# Power.net
KiCad netlist of a schematic drawn in Altium Designer
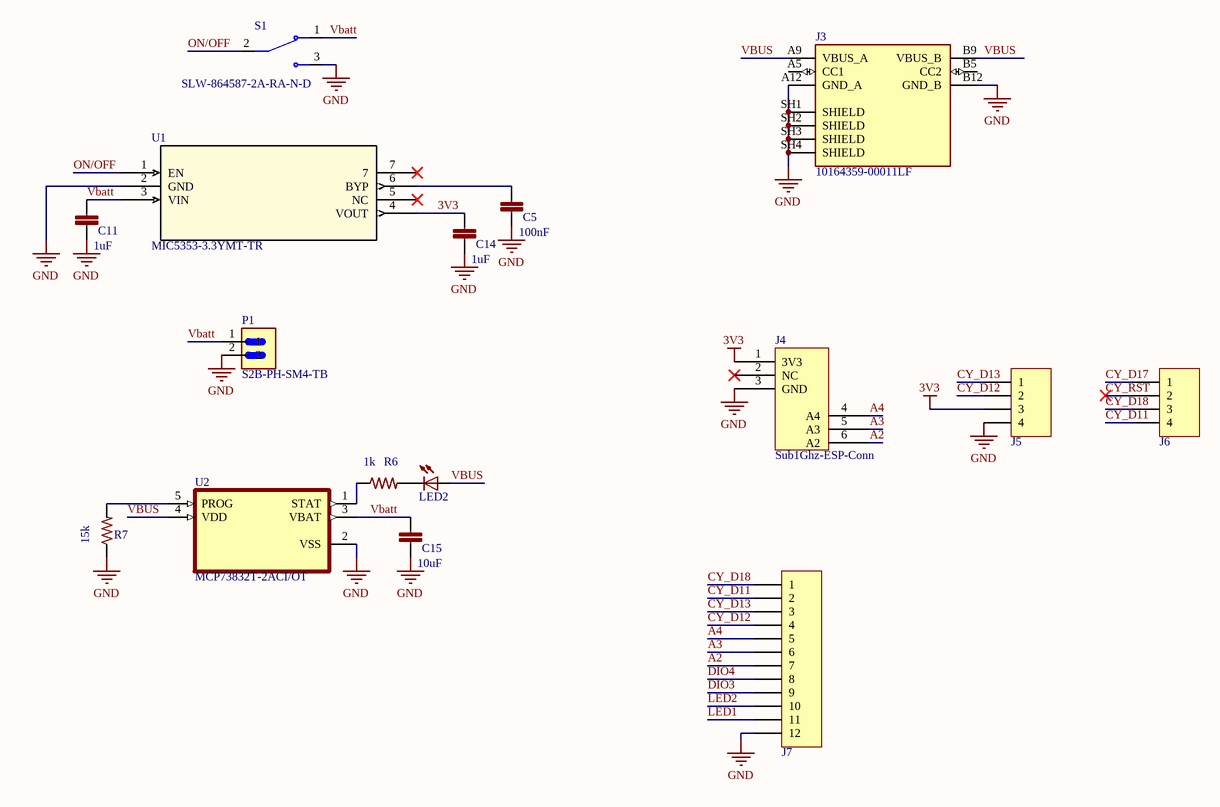
[diagram p0: Power.SchDoc]

(export (version "E")
  (design (tool "Eeschema 10.0.6"))
  (components
    (comp (ref "C5")
      (value "100nF")
      (footprint "C0402 - rounded")
      (description "Generic Capacitor SMD")
      (libsource (lib "rcl") (part "C-EU-SMD"))
    )
    (comp (ref "C11")
      (value "1uF")
      (footprint "C0402 - rounded")
      (description "Generic Capacitor SMD")
      (libsource (lib "rcl") (part "C-EU-SMD"))
    )
    (comp (ref "C14")
      (value "1uF")
      (footprint "C0402 - rounded")
      (description "Generic Capacitor SMD")
      (libsource (lib "rcl") (part "C-EU-SMD"))
    )
    (comp (ref "C15")
      (value "10uF")
      (footprint "C0603 - rounded")
      (description "Generic Capacitor SMD")
      (libsource (lib "rcl") (part "C-EU-SMD"))
    )
    (comp (ref "J3")
      (value "10164359-00011LF")
      (footprint "AMPHENOL_10164359-00011LF")
      (description "USB Type C Receptacle SMT Single Row 6Pin")
      (fields (field (name "MF") "Amphenol") (field (name "MP") "1016435900011LF"))
      (libsource (lib "Comm_Connectors") (part "10164359-00011LF"))
    )
    (comp (ref "J4")
      (value "Sub1Ghz-ESP-Conn")
      (footprint "Sub1GHz-ESP-Conn")
      (libsource (lib "Misc") (part "Sub1Ghz-ESP-Conn"))
    )
    (comp (ref "J5")
      (value "04p")
      (footprint "61300411121")
      (description "WR-PHD 2.54 mm THT Pin Header, 04p")
      (fields (field (name "PART NUMBER") "61300411121"))
      (libsource (lib "Header-254mm") (part "61300411121"))
    )
    (comp (ref "J6")
      (value "04p")
      (footprint "61300411121")
      (description "WR-PHD 2.54 mm THT Pin Header, 04p")
      (fields (field (name "PART NUMBER") "61300411121"))
      (libsource (lib "Header-254mm") (part "61300411121"))
    )
    (comp (ref "J7")
      (value "12p")
      (footprint "61301211821")
      (description "WR-PHD 2.54 mm Socket Header, 12p")
      (fields (field (name "PART NUMBER") "61301211821"))
      (libsource (lib "Header-254mm") (part "61301211821"))
    )
    (comp (ref "LED2")
      (value "LEDCHIPLED_1206")
      (footprint "CHIPLED_1206")
      (libsource (lib "led") (part "LEDCHIPLED_1206"))
    )
    (comp (ref "P1")
      (value "S2B-PH-SM4-TB")
      (footprint "JST_S2B-PH-SM4-TB")
      (description "Connector Header Surface Mount, Right Angle 2 position 0.079 (2.00mm)")
      (fields (field (name "MF") "JST Sales"))
      (libsource (lib "Misc") (part "S2B-PH-SM4-TB"))
    )
    (comp (ref "R6")
      (value "1k")
      (footprint "R0603 - rounded")
      (description "Generic Resistor SMD")
      (libsource (lib "rcl") (part "R-US-SMD"))
    )
    (comp (ref "R7")
      (value "15k")
      (footprint "R0603 - rounded")
      (description "Generic Resistor SMD")
      (libsource (lib "rcl") (part "R-US-SMD"))
    )
    (comp (ref "S1")
      (value "SLW-864587-2A-RA-N-D")
      (footprint "SW_SLW-864587-2A-RA-N-D")
      (description "8.6 x 4.5 x 8.7 mm, 2 mm Raised Slide Actuator, Right Angle, Through Hole, Slide Switch")
      (fields (field (name "MF") "Same Sky"))
      (libsource (lib "Misc") (part "SLW-864587-2A-RA-N-D"))
    )
    (comp (ref "U1")
      (value "MIC5353-3.3YMT-TR")
      (footprint "MLF-6_MT_MCH-M")
      (description "Description")
      (fields (field (name "COPYRIGHT") "Copyright (C) 2025 Ultra Librarian. All rights reserved."))
      (libsource (lib "Misc") (part "MIC5353-3.3YMT-TR"))
    )
    (comp (ref "U2")
      (value "MCP73832T-2ACI/OT")
      (footprint "SOT95P270X145-5N")
      (description "Linear Battery Charger Controller Li-Ion/Li-Pol 505mA 4.2V 5-Pin SOT-23 T/R")
      (fields (field (name "MF") "Microchip Technology"))
      (libsource (lib "Misc") (part "MCP73832T-2ACI/OT"))
    )
  )
  (nets
    (net (code "1") (name "/A2") (class "Default")
      (node (ref "J4") (pin "6") (pinfunction "A2_6") (pintype "passive"))
      (node (ref "J7") (pin "7") (pinfunction "7_7") (pintype "passive"))
    )
    (net (code "2") (name "/A3") (class "Default")
      (node (ref "J4") (pin "5") (pinfunction "A3_5") (pintype "passive"))
      (node (ref "J7") (pin "6") (pinfunction "6_6") (pintype "passive"))
    )
    (net (code "3") (name "/A4") (class "Default")
      (node (ref "J4") (pin "4") (pinfunction "A4_4") (pintype "passive"))
      (node (ref "J7") (pin "5") (pinfunction "5_5") (pintype "passive"))
    )
    (net (code "4") (name "/CY_D11") (class "Default")
      (node (ref "J6") (pin "4") (pinfunction "4_4") (pintype "passive"))
      (node (ref "J7") (pin "2") (pinfunction "2_2") (pintype "passive"))
    )
    (net (code "5") (name "/CY_D12") (class "Default")
      (node (ref "J5") (pin "2") (pinfunction "2_2") (pintype "passive"))
      (node (ref "J7") (pin "4") (pinfunction "4_4") (pintype "passive"))
    )
    (net (code "6") (name "/CY_D13") (class "Default")
      (node (ref "J5") (pin "1") (pinfunction "1_1") (pintype "passive"))
      (node (ref "J7") (pin "3") (pinfunction "3_3") (pintype "passive"))
    )
    (net (code "7") (name "/CY_D17") (class "Default")
      (node (ref "J6") (pin "1") (pinfunction "1_1") (pintype "passive"))
    )
    (net (code "8") (name "/CY_D18") (class "Default")
      (node (ref "J6") (pin "3") (pinfunction "3_3") (pintype "passive"))
      (node (ref "J7") (pin "1") (pinfunction "1_1") (pintype "passive"))
    )
    (net (code "9") (name "/CY_RST") (class "Default")
      (node (ref "J6") (pin "2") (pinfunction "2_2") (pintype "passive+no_connect"))
    )
    (net (code "10") (name "/DIO3") (class "Default")
      (node (ref "J7") (pin "9") (pinfunction "9_9") (pintype "passive"))
    )
    (net (code "11") (name "/DIO4") (class "Default")
      (node (ref "J7") (pin "8") (pinfunction "8_8") (pintype "passive"))
    )
    (net (code "12") (name "/LED1") (class "Default")
      (node (ref "J7") (pin "11") (pinfunction "11_11") (pintype "passive"))
    )
    (net (code "13") (name "/LED2") (class "Default")
      (node (ref "J7") (pin "10") (pinfunction "10_10") (pintype "passive"))
    )
    (net (code "14") (name "/ON{slash}OFF") (class "Default")
      (node (ref "S1") (pin "2") (pinfunction "2_2") (pintype "passive"))
      (node (ref "U1") (pin "1") (pinfunction "EN_1") (pintype "input"))
    )
    (net (code "15") (name "/VBUS") (class "Default")
      (node (ref "J3") (pin "A9") (pinfunction "VBUS_A_A9") (pintype "power_in"))
      (node (ref "J3") (pin "B9") (pinfunction "VBUS_B_B9") (pintype "power_in"))
      (node (ref "LED2") (pin "A") (pinfunction "A_A") (pintype "passive"))
      (node (ref "U2") (pin "4") (pinfunction "VDD_4") (pintype "input"))
    )
    (net (code "16") (name "/Vbatt") (class "Default")
      (node (ref "C11") (pin "1") (pinfunction "1_1") (pintype "passive"))
      (node (ref "C15") (pin "1") (pinfunction "1_1") (pintype "passive"))
      (node (ref "P1") (pin "1") (pinfunction "1_1") (pintype "passive"))
      (node (ref "S1") (pin "1") (pinfunction "1_1") (pintype "passive"))
      (node (ref "U1") (pin "3") (pinfunction "VIN_3") (pintype "input"))
      (node (ref "U2") (pin "3") (pinfunction "VBAT_3") (pintype "output"))
    )
    (net (code "17") (name "3V3") (class "Default")
      (node (ref "C14") (pin "1") (pinfunction "1_1") (pintype "passive"))
      (node (ref "J4") (pin "1") (pinfunction "3V3_1") (pintype "passive"))
      (node (ref "J5") (pin "3") (pinfunction "3_3") (pintype "passive"))
      (node (ref "U1") (pin "4") (pinfunction "VOUT_4") (pintype "output"))
    )
    (net (code "18") (name "GND") (class "Default")
      (node (ref "C11") (pin "2") (pinfunction "2_2") (pintype "passive"))
      (node (ref "C14") (pin "2") (pinfunction "2_2") (pintype "passive"))
      (node (ref "C15") (pin "2") (pinfunction "2_2") (pintype "passive"))
      (node (ref "C5") (pin "2") (pinfunction "2_2") (pintype "passive"))
      (node (ref "J3") (pin "A12") (pinfunction "GND_A_A12") (pintype "power_in"))
      (node (ref "J3") (pin "B12") (pinfunction "GND_B_B12") (pintype "power_in"))
      (node (ref "J3") (pin "SH1") (pinfunction "SHIELD_SH1") (pintype "passive"))
      (node (ref "J3") (pin "SH2") (pinfunction "SHIELD_SH2") (pintype "passive"))
      (node (ref "J3") (pin "SH3") (pinfunction "SHIELD_SH3") (pintype "passive"))
      (node (ref "J3") (pin "SH4") (pinfunction "SHIELD_SH4") (pintype "passive"))
      (node (ref "J4") (pin "3") (pinfunction "GND_3") (pintype "passive"))
      (node (ref "J5") (pin "4") (pinfunction "4_4") (pintype "passive"))
      (node (ref "J7") (pin "12") (pinfunction "12_12") (pintype "passive"))
      (node (ref "P1") (pin "2") (pinfunction "2_2") (pintype "passive"))
      (node (ref "R7") (pin "1") (pinfunction "1_1") (pintype "passive"))
      (node (ref "S1") (pin "3") (pinfunction "3_3") (pintype "passive"))
      (node (ref "U1") (pin "2") (pinfunction "GND_2") (pintype "power_in"))
      (node (ref "U2") (pin "2") (pinfunction "VSS_2") (pintype "power_in"))
    )
    (net (code "19") (name "Net-(LED2-PadC)") (class "Default")
      (node (ref "LED2") (pin "C") (pinfunction "C_C") (pintype "passive"))
      (node (ref "R6") (pin "2") (pinfunction "2_2") (pintype "passive"))
    )
    (net (code "20") (name "Net-(U1-BYP)") (class "Default")
      (node (ref "C5") (pin "1") (pinfunction "1_1") (pintype "passive"))
      (node (ref "U1") (pin "6") (pinfunction "BYP_6") (pintype "output"))
    )
    (net (code "21") (name "Net-(U2-PROG)") (class "Default")
      (node (ref "R7") (pin "2") (pinfunction "2_2") (pintype "passive"))
      (node (ref "U2") (pin "5") (pinfunction "PROG_5") (pintype "input"))
    )
    (net (code "22") (name "Net-(U2-STAT)") (class "Default")
      (node (ref "R6") (pin "1") (pinfunction "1_1") (pintype "passive"))
      (node (ref "U2") (pin "1") (pinfunction "STAT_1") (pintype "output"))
    )
    (net (code "23") (name "unconnected-(J3-CC1-PadA5)") (class "Default")
      (node (ref "J3") (pin "A5") (pinfunction "CC1_A5") (pintype "bidirectional"))
    )
    (net (code "24") (name "unconnected-(J3-CC2-PadB5)") (class "Default")
      (node (ref "J3") (pin "B5") (pinfunction "CC2_B5") (pintype "bidirectional"))
    )
    (net (code "25") (name "unconnected-(J4-NC-Pad2)") (class "Default")
      (node (ref "J4") (pin "2") (pinfunction "NC_2") (pintype "passive+no_connect"))
    )
    (net (code "26") (name "unconnected-(U1-NC-Pad5)") (class "Default")
      (node (ref "U1") (pin "5") (pinfunction "NC_5") (pintype "passive+no_connect"))
    )
    (net (code "27") (name "unconnected-(U1-Pad7)") (class "Default")
      (node (ref "U1") (pin "7") (pinfunction "7_7") (pintype "passive+no_connect"))
    )
  )
)
